# SH5_-_CAN.net
KiCad netlist of a schematic drawn in Altium Designer
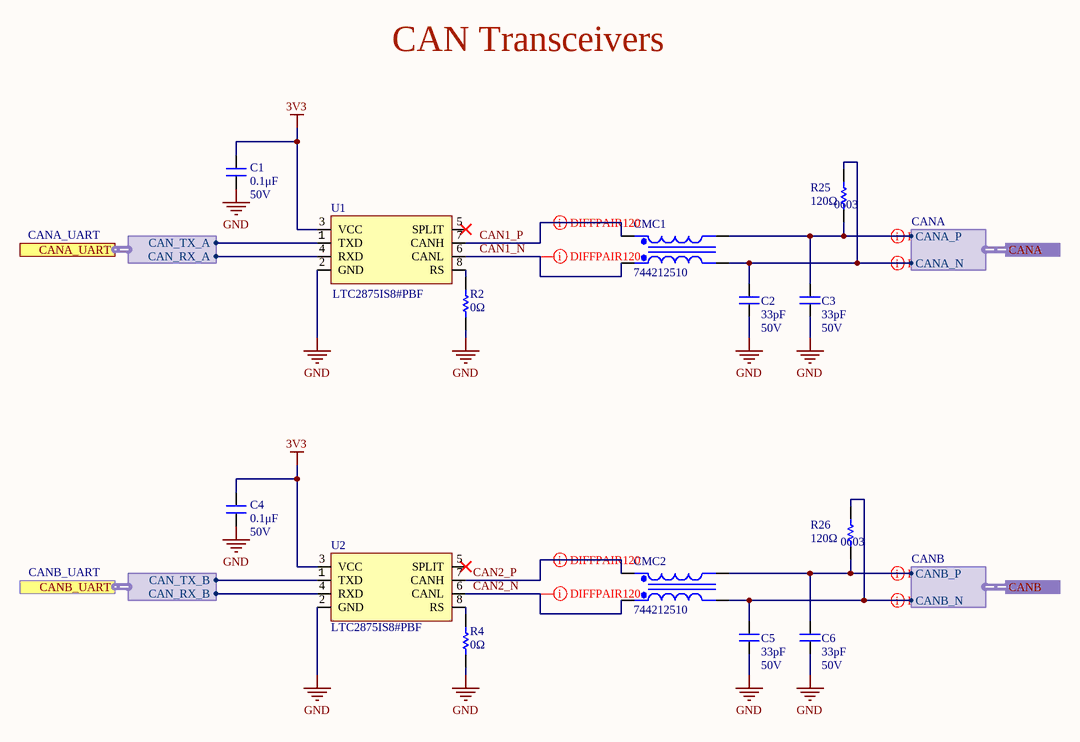
[diagram p0: SH5 - CAN.SchDoc]

(export (version "E")
  (design (tool "Eeschema 10.0.6"))
  (components
    (comp (ref "C1")
      (value "0.1μF")
      (footprint "CAP0603")
      (description "CAP CER 0.1UF 50V X7R 0603")
      (fields (field (name "VOLTAGE RATING") "50V") (field (name "Comment") "CAP_0.1uF_50V_0603"))
      (libsource (lib "UWRT_Schematic_Library_2020") (part "CAP_0.1uF_50V_0603"))
    )
    (comp (ref "C2")
      (value "33pF")
      (footprint "CAP0603")
      (description "CAP CER 33PF 50V C0G/NP0")
      (fields
        (field (name "TOLERANCE") "5%")
        (field (name "VOLTAGE") "50V")
        (field (name "Comment") "CAP_33pF_50V_0603")
      )
      (libsource (lib "UWRT_Schematic_Library_2020") (part "CAP_33pF_50V_0603"))
    )
    (comp (ref "C3")
      (value "33pF")
      (footprint "CAP0603")
      (description "CAP CER 33PF 50V C0G/NP0")
      (fields
        (field (name "TOLERANCE") "5%")
        (field (name "VOLTAGE") "50V")
        (field (name "Comment") "CAP_33pF_50V_0603")
      )
      (libsource (lib "UWRT_Schematic_Library_2020") (part "CAP_33pF_50V_0603"))
    )
    (comp (ref "C4")
      (value "0.1μF")
      (footprint "CAP0603")
      (description "CAP CER 0.1UF 50V X7R 0603")
      (fields (field (name "VOLTAGE RATING") "50V") (field (name "Comment") "CAP_0.1uF_50V_0603"))
      (libsource (lib "UWRT_Schematic_Library_2020") (part "CAP_0.1uF_50V_0603"))
    )
    (comp (ref "C5")
      (value "33pF")
      (footprint "CAP0603")
      (description "CAP CER 33PF 50V C0G/NP0")
      (fields
        (field (name "TOLERANCE") "5%")
        (field (name "VOLTAGE") "50V")
        (field (name "Comment") "CAP_33pF_50V_0603")
      )
      (libsource (lib "UWRT_Schematic_Library_2020") (part "CAP_33pF_50V_0603"))
    )
    (comp (ref "C6")
      (value "33pF")
      (footprint "CAP0603")
      (description "CAP CER 33PF 50V C0G/NP0")
      (fields
        (field (name "TOLERANCE") "5%")
        (field (name "VOLTAGE") "50V")
        (field (name "Comment") "CAP_33pF_50V_0603")
      )
      (libsource (lib "UWRT_Schematic_Library_2020") (part "CAP_33pF_50V_0603"))
    )
    (comp (ref "CMC1")
      (value "CMC_51uH")
      (footprint "744212510")
      (description "CMC 51uH 300MA 2LN SMD")
      (fields (field (name "MANUFACTURER PART NUMBER 1") "744212510") (field (name "TOLERANCE") "50%"))
      (libsource (lib "UWRT_Schematic_Library_2020") (part "CMC_51uH"))
    )
    (comp (ref "CMC2")
      (value "CMC_51uH")
      (footprint "744212510")
      (description "CMC 51uH 300MA 2LN SMD")
      (fields (field (name "MANUFACTURER PART NUMBER 1") "744212510") (field (name "TOLERANCE") "50%"))
      (libsource (lib "UWRT_Schematic_Library_2020") (part "CMC_51uH"))
    )
    (comp (ref "R2")
      (value "0Ω")
      (footprint "RESC0603")
      (description "RES 0 OHM JUMPER 1/10W 0603")
      (fields (field (name "Comment") "RES_0Ω_0603"))
      (libsource (lib "UWRT_Schematic_Library_2020") (part "RES_0Ω_0603"))
    )
    (comp (ref "R4")
      (value "0Ω")
      (footprint "RESC0603")
      (description "RES 0 OHM JUMPER 1/10W 0603")
      (fields (field (name "Comment") "RES_0Ω_0603"))
      (libsource (lib "UWRT_Schematic_Library_2020") (part "RES_0Ω_0603"))
    )
    (comp (ref "R25")
      (value "120Ω")
      (footprint "RESC0603")
      (description "RES 120 OHM 5% 1/10W 0603")
      (fields (field (name "PACKAGE/FOOTPRINT") "0603") (field (name "Comment") "RES_120Ω_0603"))
      (libsource (lib "UWRT_Schematic_Library_2020") (part "RES_120Ω_0603_5%"))
    )
    (comp (ref "R26")
      (value "120Ω")
      (footprint "RESC0603")
      (description "RES 120 OHM 5% 1/10W 0603")
      (fields (field (name "PACKAGE/FOOTPRINT") "0603") (field (name "Comment") "RES_120Ω_0603"))
      (libsource (lib "UWRT_Schematic_Library_2020") (part "RES_120Ω_0603_5%"))
    )
    (comp (ref "U1")
      (value "LTC2875")
      (footprint "LT-S8_N")
      (description "IC TXRX CAN 4MBPS 8SO")
      (fields
        (field (name "MANUFACTURER PART NUMBER 1") "LTC2875IS8#PBF")
        (field (name "LCSC PART #") "C117076")
      )
      (libsource (lib "UWRT_Schematic_Library_2020") (part "LTC2875"))
    )
    (comp (ref "U2")
      (value "LTC2875")
      (footprint "LT-S8_N")
      (description "IC TXRX CAN 4MBPS 8SO")
      (fields
        (field (name "MANUFACTURER PART NUMBER 1") "LTC2875IS8#PBF")
        (field (name "LCSC PART #") "C117076")
      )
      (libsource (lib "UWRT_Schematic_Library_2020") (part "LTC2875"))
    )
  )
  (nets
    (net (code "5") (name "/CAN1_N") (class "Default")
      (node (ref "CMC1") (pin "1") (pinfunction "Pri+_1") (pintype "passive"))
      (node (ref "U1") (pin "6") (pinfunction "CANL_6") (pintype "passive"))
    )
    (net (code "6") (name "/CAN1_P") (class "Default")
      (node (ref "CMC1") (pin "3") (pinfunction "Sec+_3") (pintype "passive"))
      (node (ref "U1") (pin "7") (pinfunction "CANH_7") (pintype "passive"))
    )
    (net (code "7") (name "/CAN2_N") (class "Default")
      (node (ref "CMC2") (pin "1") (pinfunction "Pri+_1") (pintype "passive"))
      (node (ref "U2") (pin "6") (pinfunction "CANL_6") (pintype "passive"))
    )
    (net (code "8") (name "/CAN2_P") (class "Default")
      (node (ref "CMC2") (pin "3") (pinfunction "Sec+_3") (pintype "passive"))
      (node (ref "U2") (pin "7") (pinfunction "CANH_7") (pintype "passive"))
    )
    (net (code "9") (name "/CANA_N") (class "Default")
      (node (ref "C2") (pin "2") (pinfunction "2_2") (pintype "passive"))
      (node (ref "CMC1") (pin "5") (pinfunction "Pri-_5") (pintype "passive"))
      (node (ref "R25") (pin "2") (pinfunction "2_2") (pintype "passive"))
    )
    (net (code "10") (name "/CANA_P") (class "Default")
      (node (ref "C3") (pin "2") (pinfunction "2_2") (pintype "passive"))
      (node (ref "CMC1") (pin "4") (pinfunction "Sec-_4") (pintype "passive"))
      (node (ref "R25") (pin "1") (pinfunction "1_1") (pintype "passive"))
    )
    (net (code "11") (name "/CANB_N") (class "Default")
      (node (ref "C5") (pin "2") (pinfunction "2_2") (pintype "passive"))
      (node (ref "CMC2") (pin "5") (pinfunction "Pri-_5") (pintype "passive"))
      (node (ref "R26") (pin "2") (pinfunction "2_2") (pintype "passive"))
    )
    (net (code "12") (name "/CANB_P") (class "Default")
      (node (ref "C6") (pin "2") (pinfunction "2_2") (pintype "passive"))
      (node (ref "CMC2") (pin "4") (pinfunction "Sec-_4") (pintype "passive"))
      (node (ref "R26") (pin "1") (pinfunction "1_1") (pintype "passive"))
    )
    (net (code "13") (name "/CAN_RX_A") (class "Default")
      (node (ref "U1") (pin "4") (pinfunction "RXD_4") (pintype "passive"))
    )
    (net (code "14") (name "/CAN_RX_B") (class "Default")
      (node (ref "U2") (pin "4") (pinfunction "RXD_4") (pintype "passive"))
    )
    (net (code "15") (name "/CAN_TX_A") (class "Default")
      (node (ref "U1") (pin "1") (pinfunction "TXD_1") (pintype "passive"))
    )
    (net (code "16") (name "/CAN_TX_B") (class "Default")
      (node (ref "U2") (pin "1") (pinfunction "TXD_1") (pintype "passive"))
    )
    (net (code "21") (name "3V3") (class "Default")
      (node (ref "C1") (pin "1") (pinfunction "1_1") (pintype "passive"))
      (node (ref "C4") (pin "1") (pinfunction "1_1") (pintype "passive"))
      (node (ref "U1") (pin "3") (pinfunction "VCC_3") (pintype "passive"))
      (node (ref "U2") (pin "3") (pinfunction "VCC_3") (pintype "passive"))
    )
    (net (code "22") (name "GND") (class "Default")
      (node (ref "C1") (pin "2") (pinfunction "2_2") (pintype "passive"))
      (node (ref "C2") (pin "1") (pinfunction "1_1") (pintype "passive"))
      (node (ref "C3") (pin "1") (pinfunction "1_1") (pintype "passive"))
      (node (ref "C4") (pin "2") (pinfunction "2_2") (pintype "passive"))
      (node (ref "C5") (pin "1") (pinfunction "1_1") (pintype "passive"))
      (node (ref "C6") (pin "1") (pinfunction "1_1") (pintype "passive"))
      (node (ref "R2") (pin "1") (pinfunction "1_1") (pintype "passive"))
      (node (ref "R4") (pin "1") (pinfunction "1_1") (pintype "passive"))
      (node (ref "U1") (pin "2") (pinfunction "GND_2") (pintype "passive"))
      (node (ref "U2") (pin "2") (pinfunction "GND_2") (pintype "passive"))
    )
    (net (code "23") (name "Net-(U1-RS)") (class "Default")
      (node (ref "R2") (pin "2") (pinfunction "2_2") (pintype "passive"))
      (node (ref "U1") (pin "8") (pinfunction "RS_8") (pintype "passive"))
    )
    (net (code "24") (name "Net-(U2-RS)") (class "Default")
      (node (ref "R4") (pin "2") (pinfunction "2_2") (pintype "passive"))
      (node (ref "U2") (pin "8") (pinfunction "RS_8") (pintype "passive"))
    )
    (net (code "25") (name "unconnected-(U1-SPLIT-Pad5)") (class "Default")
      (node (ref "U1") (pin "5") (pinfunction "SPLIT_5") (pintype "passive+no_connect"))
    )
    (net (code "26") (name "unconnected-(U2-SPLIT-Pad5)") (class "Default")
      (node (ref "U2") (pin "5") (pinfunction "SPLIT_5") (pintype "passive+no_connect"))
    )
  )
)
